# Flyback_Converter_SCHEMATIC.net
KiCad netlist of a schematic drawn in Altium Designer
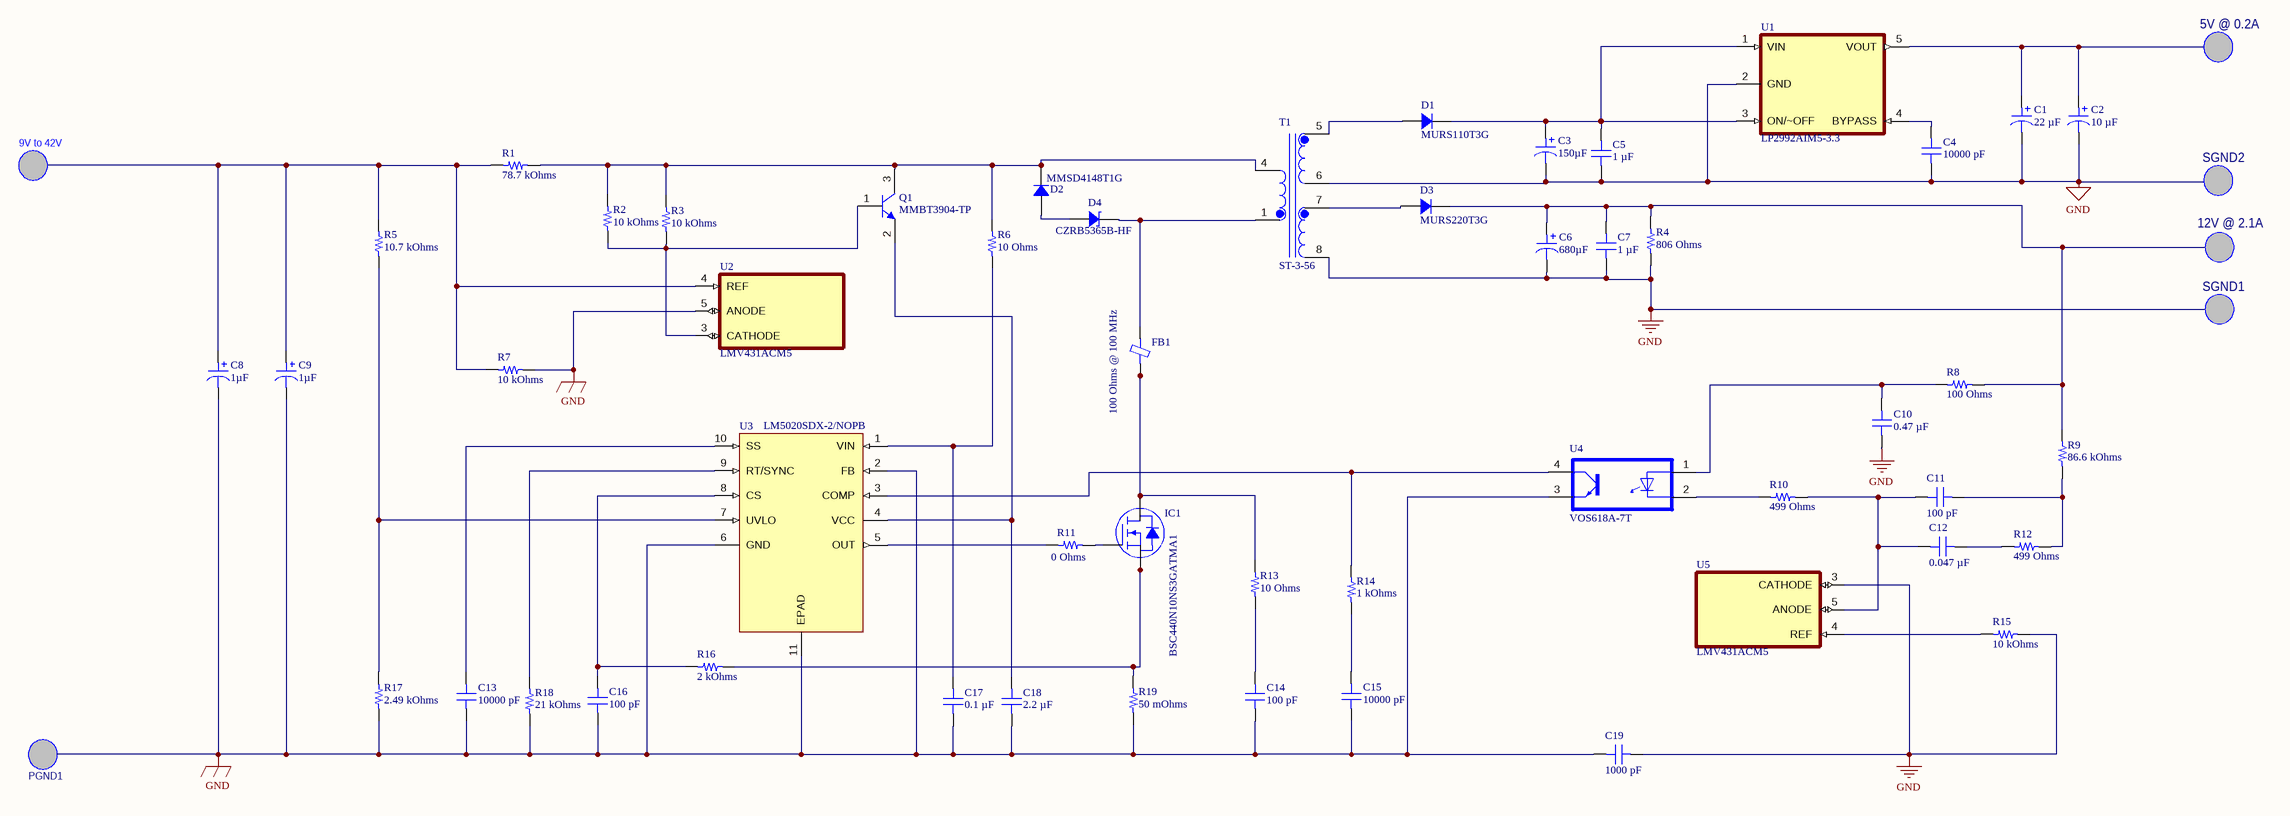
[diagram p0: Flyback Converter SCHEMATIC.SchDoc]

(export (version "E")
  (design (tool "Eeschema 10.0.6"))
  (components
    (comp (ref "C1")
      (value "22 µF")
      (footprint "CAP AL TH D8 L3.5 H12.5")
      (description "CAP ALUM 22UF 20% 100V RADIAL")
      (fields (field (name "PART NUMBER") "UPJ2A220MPD") (field (name "MANUFACTURER") "Nichicon"))
      (libsource (lib "Celestial Altium Library - altium_library") (part "Polarised Capacitor"))
    )
    (comp (ref "C2")
      (value "10 µF")
      (footprint "CAP AL TH D8 L3.5 H12.5")
      (description "CAP ALUM 10UF 20% 100V RADIAL")
      (fields (field (name "PART NUMBER") "UKL2A100MPD1TD") (field (name "MANUFACTURER") "Nichicon"))
      (libsource (lib "Celestial Altium Library - altium_library") (part "Polarised Capacitor"))
    )
    (comp (ref "C3")
      (value "150µF")
      (footprint "CAP TH ALUM ELEC D8.00mm S3.50mm H13.00mm")
      (description "CAP ALUM 150UF 20% 35V RADIAL")
      (fields
        (field (name "PART NUMBER") "EKZE350ELL151MHB5D")
        (field (name "MANUFACTURER") "United Chemi-Con")
      )
      (libsource (lib "Celestial Altium Library - altium_library") (part "Polarised Capacitor"))
    )
    (comp (ref "C4")
      (value "10000 pF")
      (footprint "CAP 1206_3216 - 0.8MM")
      (description "CAP CER 1206 10NF 200V X7R 10%")
      (fields (field (name "PART NUMBER") "C1206C103K2REC7800") (field (name "MANUFACTURER") "KEMET"))
      (libsource (lib "Celestial Altium Library - altium_library") (part "Capacitor"))
    )
    (comp (ref "C5")
      (value "1 µF")
      (footprint "CAP 1206_3216 - 0.8MM")
      (description "CAP CER 1UF 100V X7R 1206")
      (fields (field (name "PART NUMBER") "C1206C105K1RACAUTO") (field (name "MANUFACTURER") "KEMET"))
      (libsource (lib "Celestial Altium Library - altium_library") (part "Capacitor"))
    )
    (comp (ref "C6")
      (value "680µF")
      (footprint "CAP TH ALUM ELEC D10.00mm S5.00mm H14.00mm")
      (description "CAP ALUM 680UF 20% 25V RADIAL")
      (fields (field (name "PART NUMBER") "25PX680MEFC10X12.5") (field (name "MANUFACTURER") "Rubycon"))
      (libsource (lib "Celestial Altium Library - altium_library") (part "Polarised Capacitor"))
    )
    (comp (ref "C7")
      (value "1 µF")
      (footprint "CAP 1206_3216 - 0.8MM")
      (description "CAP CER 1UF 100V X7R 1206")
      (fields (field (name "PART NUMBER") "C1206C105K1RACAUTO") (field (name "MANUFACTURER") "KEMET"))
      (libsource (lib "Celestial Altium Library - altium_library") (part "Capacitor"))
    )
    (comp (ref "C8")
      (value "1µF")
      (footprint "CAP TH ALUM ELEC D5.00mm S2.00mm H12.50mm")
      (description "CAP ALUM 1UF 20% 100V RADIAL")
      (fields (field (name "PART NUMBER") "UVP2A010MDD") (field (name "MANUFACTURER") "Nichicon"))
      (libsource (lib "Celestial Altium Library - altium_library") (part "Polarised Capacitor"))
    )
    (comp (ref "C9")
      (value "1µF")
      (footprint "CAP TH ALUM ELEC D5.00mm S2.00mm H12.50mm")
      (description "CAP ALUM 1UF 20% 100V RADIAL")
      (fields (field (name "PART NUMBER") "UVP2A010MDD") (field (name "MANUFACTURER") "Nichicon"))
      (libsource (lib "Celestial Altium Library - altium_library") (part "Polarised Capacitor"))
    )
    (comp (ref "C10")
      (value "0.47 µF")
      (footprint "CAP 1206_3216 - 0.8MM")
      (description "CAP CER 0.47UF 100V X7R 1206")
      (fields
        (field (name "PART NUMBER") "CGA5L2X7R2A474M160AE")
        (field (name "MANUFACTURER") "TDK Corporation")
      )
      (libsource (lib "Celestial Altium Library - altium_library") (part "Capacitor"))
    )
    (comp (ref "C11")
      (value "100 pF")
      (footprint "CAP 1206_3216 - 0.8MM")
      (description "CAP CER 100PF 100V X8R 1206")
      (fields (field (name "PART NUMBER") "C1206C101F1HAC7800") (field (name "MANUFACTURER") "KEMET"))
      (libsource (lib "Celestial Altium Library - altium_library") (part "Capacitor"))
    )
    (comp (ref "C12")
      (value "0.047 µF")
      (footprint "CAP 1206_3216 - 0.8MM")
      (description "CAP CER 1206 47NF 250V X7R 10%")
      (fields (field (name "PART NUMBER") "C1206C473KAREC7800") (field (name "MANUFACTURER") "KEMET"))
      (libsource (lib "Celestial Altium Library - altium_library") (part "Capacitor"))
    )
    (comp (ref "C13")
      (value "10000 pF")
      (footprint "CAP 1206_3216 - 0.8MM")
      (description "CAP CER 1206 10NF 200V X7R 10%")
      (fields (field (name "PART NUMBER") "C1206C103K2REC7800") (field (name "MANUFACTURER") "KEMET"))
      (libsource (lib "Celestial Altium Library - altium_library") (part "Capacitor"))
    )
    (comp (ref "C14")
      (value "100 pF")
      (footprint "CAP 1206_3216 - 0.8MM")
      (description "CAP CER 100PF 100V C0G/NP0 1206")
      (fields (field (name "PART NUMBER") "C1206C101K1GAC7800") (field (name "MANUFACTURER") "KEMET"))
      (libsource (lib "Celestial Altium Library - altium_library") (part "Capacitor"))
    )
    (comp (ref "C15")
      (value "10000 pF")
      (footprint "CAP 1206_3216 - 0.8MM")
      (description "CAP CER 1206 10NF 200V X7R 10%")
      (fields (field (name "PART NUMBER") "C1206C103K2REC7800") (field (name "MANUFACTURER") "KEMET"))
      (libsource (lib "Celestial Altium Library - altium_library") (part "Capacitor"))
    )
    (comp (ref "C16")
      (value "100 pF")
      (footprint "CAP 1206_3216 - 0.8MM")
      (description "CAP CER 100PF 100V C0G/NP0 1206")
      (fields (field (name "PART NUMBER") "C1206C101K1GAC7800") (field (name "MANUFACTURER") "KEMET"))
      (libsource (lib "Celestial Altium Library - altium_library") (part "Capacitor"))
    )
    (comp (ref "C17")
      (value "0.1 µF")
      (footprint "CAP 1206_3216 - 0.8MM")
      (description "SMD AUTO X7R FE, CERAMIC, 0.1 UF")
      (fields (field (name "PART NUMBER") "C1206S104K5RACAUTO") (field (name "MANUFACTURER") "KEMET"))
      (libsource (lib "Celestial Altium Library - altium_library") (part "Capacitor"))
    )
    (comp (ref "C18")
      (value "2.2 µF")
      (footprint "CAP 1206_3216 - 0.8MM")
      (description "SMD AUTO X7R FO, CERAMIC, 2.2 UF")
      (fields (field (name "PART NUMBER") "C1206J225J4RACAUTO") (field (name "MANUFACTURER") "KEMET"))
      (libsource (lib "Celestial Altium Library - altium_library") (part "Capacitor"))
    )
    (comp (ref "C19")
      (value "1000 pF")
      (footprint "CAP 1206_3216 - 0.8MM")
      (description "CAP CER 1206 1NF 200V C0G 2%")
      (fields (field (name "PART NUMBER") "C1206C102G2GECAUTO") (field (name "MANUFACTURER") "KEMET"))
      (libsource (lib "Celestial Altium Library - altium_library") (part "Capacitor"))
    )
    (comp (ref "D1")
      (value "MURS110T3G")
      (footprint "DO214AA SMB")
      (description "DIODE GEN PURP 100V 2A SMB")
      (fields (field (name "MANUFACTURER") "ON Semiconductor"))
      (libsource (lib "Celestial Altium Library - altium_library") (part "Diode"))
    )
    (comp (ref "D2")
      (value "MMSD4148T1G")
      (footprint "SOD-123")
      (description "DIODE GEN PURP 100V 200MA SOD123")
      (fields (field (name "MANUFACTURER") "ON Semiconductor"))
      (libsource (lib "Celestial Altium Library - altium_library") (part "Diode"))
    )
    (comp (ref "D3")
      (value "MURS220T3G")
      (footprint "DO214AA SMB")
      (description "DIODE GEN PURP 200V 2A SMB")
      (fields (field (name "MANUFACTURER") "ON Semiconductor"))
      (libsource (lib "Celestial Altium Library - altium_library") (part "Diode"))
    )
    (comp (ref "D4")
      (value "CZRB5365B-HF")
      (footprint "DO214AA SMB")
      (description "DIODE ZENER 36V 5W DO214AA")
      (fields (field (name "MANUFACTURER") "Comchip Technology") (field (name "TOLERANCE") "±5%"))
      (libsource (lib "Celestial Altium Library - altium_library") (part "Diode Zener"))
    )
    (comp (ref "FB1")
      (value "100 Ohms @ 100 MHz")
      (footprint "FER 1206_3216")
      (description "FIXED IND 100 3000MA 1206")
      (fields
        (field (name "PART NUMBER") "MFBW1V3216-101-R")
        (field (name "MANUFACTURER") "Eaton - Electronics Division")
      )
      (libsource (lib "Celestial Altium Library - altium_library") (part "Ferrite Chip"))
    )
    (comp (ref "IC1")
      (value "BSC440N10NS3GATMA1")
      (footprint "INFINEON PG-TDSON-8 6.15X5.32MM")
      (description "MOSFET N-CH 100V 5.3A/18A TDSON")
      (fields (field (name "MANUFACTURER") "Infineon Technologies"))
      (libsource (lib "Celestial Altium Library - altium_library") (part "INFINEON BSC MOSFET N-CH"))
    )
    (comp (ref "Q1")
      (value "MMBT3904-TP")
      (footprint "MCCSEMI SOT-23-3")
      (description "TRANS NPN 40V 0.2A SOT23")
      (fields (field (name "MANUFACTURER") "Micro Commercial Co"))
      (libsource (lib "Celestial Altium Library - altium_library") (part "MCCSEMI NPN SOT-23-3"))
    )
    (comp (ref "R1")
      (value "78.7 kOhms")
      (footprint "RES 1206_3216")
      (description "RES SMD 78.7K OHM 1% 1/4W 1206")
      (fields (field (name "PART NUMBER") "CRCW120678K7FKEA") (field (name "MANUFACTURER") "Vishay Dale"))
      (libsource (lib "Celestial Altium Library - altium_library") (part "Resistor"))
    )
    (comp (ref "R2")
      (value "10 kOhms")
      (footprint "RES 1206_3216")
      (description "RES SMD 10K OHM 1% 1/4W 1206")
      (fields
        (field (name "PART NUMBER") "CRG1206F10K")
        (field (name "MANUFACTURER") "TE Connectivity Passive Product")
      )
      (libsource (lib "Celestial Altium Library - altium_library") (part "Resistor"))
    )
    (comp (ref "R3")
      (value "10 kOhms")
      (footprint "RES 1206_3216")
      (description "RES SMD 10K OHM 1% 1/4W 1206")
      (fields
        (field (name "PART NUMBER") "CRG1206F10K")
        (field (name "MANUFACTURER") "TE Connectivity Passive Product")
      )
      (libsource (lib "Celestial Altium Library - altium_library") (part "Resistor"))
    )
    (comp (ref "R4")
      (value "806 Ohms")
      (footprint "RES 1206_3216")
      (description "RES SMD 806 OHM 1% 1/4W 1206")
      (fields (field (name "PART NUMBER") "CRCW1206806RFKEA") (field (name "MANUFACTURER") "Vishay Dale"))
      (libsource (lib "Celestial Altium Library - altium_library") (part "Resistor"))
    )
    (comp (ref "R5")
      (value "10.7 kOhms")
      (footprint "RES 1206_3216")
      (description "RES 10.7K OHM 1% 1/4W 1206")
      (fields (field (name "PART NUMBER") "RC1206FR-0710K7L") (field (name "MANUFACTURER") "Yageo"))
      (libsource (lib "Celestial Altium Library - altium_library") (part "Resistor"))
    )
    (comp (ref "R6")
      (value "10 Ohms")
      (footprint "RES 1206_3216")
      (description "RES SMD 10 OHM 1% 1/4W 1206")
      (fields (field (name "PART NUMBER") "CRCW120610R0FKEB") (field (name "MANUFACTURER") "Vishay Dale"))
      (libsource (lib "Celestial Altium Library - altium_library") (part "Resistor"))
    )
    (comp (ref "R7")
      (value "10 kOhms")
      (footprint "RES 1206_3216")
      (description "RES SMD 10K OHM 1% 1/4W 1206")
      (fields
        (field (name "PART NUMBER") "CRG1206F10K")
        (field (name "MANUFACTURER") "TE Connectivity Passive Product")
      )
      (libsource (lib "Celestial Altium Library - altium_library") (part "Resistor"))
    )
    (comp (ref "R8")
      (value "100 Ohms")
      (footprint "RES 1206_3216")
      (description "RES SMD 100 OHM 1% 1/4W 1206")
      (fields (field (name "PART NUMBER") "CRCW1206100RFKEB") (field (name "MANUFACTURER") "Vishay Dale"))
      (libsource (lib "Celestial Altium Library - altium_library") (part "Resistor"))
    )
    (comp (ref "R9")
      (value "86.6 kOhms")
      (footprint "RES 1206_3216")
      (description "RES SMD 86.6K OHM 1% 1/4W 1206")
      (fields (field (name "PART NUMBER") "CRCW120686K6FKEA") (field (name "MANUFACTURER") "Vishay Dale"))
      (libsource (lib "Celestial Altium Library - altium_library") (part "Resistor"))
    )
    (comp (ref "R10")
      (value "499 Ohms")
      (footprint "RES 1206_3216")
      (description "RES SMD 499 OHM 1% 1/4W 1206")
      (fields (field (name "PART NUMBER") "CR1206-FX-4990ELF") (field (name "MANUFACTURER") "Bourns Inc."))
      (libsource (lib "Celestial Altium Library - altium_library") (part "Resistor"))
    )
    (comp (ref "R11")
      (value "0 Ohms")
      (footprint "RES 1206_3216")
      (description "RES SMD 0 OHM JUMPER 1/4W 1206")
      (fields (field (name "PART NUMBER") "CRCW12060000ZSTA") (field (name "MANUFACTURER") "Vishay Dale"))
      (libsource (lib "Celestial Altium Library - altium_library") (part "Resistor"))
    )
    (comp (ref "R12")
      (value "499 Ohms")
      (footprint "RES 1206_3216")
      (description "RES SMD 499 OHM 1% 1/4W 1206")
      (fields (field (name "PART NUMBER") "CR1206-FX-4990ELF") (field (name "MANUFACTURER") "Bourns Inc."))
      (libsource (lib "Celestial Altium Library - altium_library") (part "Resistor"))
    )
    (comp (ref "R13")
      (value "10 Ohms")
      (footprint "RES 1206_3216")
      (description "RES SMD 10 OHM 1% 1/4W 1206")
      (fields (field (name "PART NUMBER") "CRCW120610R0FKEB") (field (name "MANUFACTURER") "Vishay Dale"))
      (libsource (lib "Celestial Altium Library - altium_library") (part "Resistor"))
    )
    (comp (ref "R14")
      (value "1 kOhms")
      (footprint "RES 1206_3216")
      (description "RES 1K OHM 1% 1/4W 1206")
      (fields (field (name "PART NUMBER") "CRCW12061K00FKEBC") (field (name "MANUFACTURER") "Vishay Dale"))
      (libsource (lib "Celestial Altium Library - altium_library") (part "Resistor"))
    )
    (comp (ref "R15")
      (value "10 kOhms")
      (footprint "RES 1206_3216")
      (description "RES SMD 10K OHM 1% 1/4W 1206")
      (fields
        (field (name "PART NUMBER") "CRG1206F10K")
        (field (name "MANUFACTURER") "TE Connectivity Passive Product")
      )
      (libsource (lib "Celestial Altium Library - altium_library") (part "Resistor"))
    )
    (comp (ref "R16")
      (value "2 kOhms")
      (footprint "RES 1206_3216")
      (description "RES SMD 2K OHM 1% 1/4W 1206")
      (fields (field (name "PART NUMBER") "CRCW12062K00FKEA") (field (name "MANUFACTURER") "Vishay Dale"))
      (libsource (lib "Celestial Altium Library - altium_library") (part "Resistor"))
    )
    (comp (ref "R17")
      (value "2.49 kOhms")
      (footprint "RES 1206_3216")
      (description "RES SMD 2.49K OHM 1% 1/4W 1206")
      (fields (field (name "PART NUMBER") "CRCW12062K49FKEA") (field (name "MANUFACTURER") "Vishay Dale"))
      (libsource (lib "Celestial Altium Library - altium_library") (part "Resistor"))
    )
    (comp (ref "R18")
      (value "21 kOhms")
      (footprint "RES 1206_3216")
      (description "RES SMD 21K OHM 1% 1/4W 1206")
      (fields (field (name "PART NUMBER") "CRCW120621K0FKEA") (field (name "MANUFACTURER") "Vishay Dale"))
      (libsource (lib "Celestial Altium Library - altium_library") (part "Resistor"))
    )
    (comp (ref "R19")
      (value "50 mOhms")
      (footprint "RES 1206_3216")
      (description "RES 0.05 OHM 1% 1/4W 1206")
      (fields (field (name "PART NUMBER") "RL1206FR-070R05L") (field (name "MANUFACTURER") "Yageo"))
      (libsource (lib "Celestial Altium Library - altium_library") (part "Resistor"))
    )
    (comp (ref "T1")
      (value "ST-3-56")
      (footprint "Flyback Transformer:flyback tranformer")
      (description "Split Bobbin Low Power Transformer ¦ 2.4VA Power ¦ 115V Input ¦ 10VCT Output Series")
      (libsource (lib "ST-3-56") (part "ST-3-56"))
    )
    (comp (ref "U1")
      (value "LP2992AIM5-3.3")
      (footprint "SOT95P280X145-5N:SOT95P280X145-5N")
      (libsource (lib "LP2992AIM5-3.3") (part "LP2992AIM5-3.3"))
    )
    (comp (ref "U2")
      (value "LMV431ACM5")
      (footprint "SOT95P280X145-5N-1:SOT95P280X145-5N")
      (description "1%, low-voltage (1.24-V) adjustable precision shunt regulator 5-SOT-23 0 to 70")
      (fields (field (name "MF") "Texas Instruments"))
      (libsource (lib "") (part "LMV431ACM5_1"))
    )
    (comp (ref "U3")
      (value "LM5020SDX-2/NOPB")
      (footprint "DFN400X400X80-11N:DFN400X400X80-11N")
      (description "13-100V Wide Vin, Current Mode PWM Boost, Flyback, Sepic Controller")
      (fields (field (name "MF") "Texas Instruments"))
      (libsource (lib "LM5020SDX-2_NOPB") (part "LM5020SDX-2/NOPB"))
    )
    (comp (ref "U4")
      (value "VOS618A-7T")
      (footprint "SOIC127P700X210-4N:SOIC127P700X210-4N")
      (description "Optoisolator Transistor Output 3750Vrms 1 Channel 4-SSOP")
      (fields (field (name "MF") "Vishay"))
      (libsource (lib "VOS618A-7T") (part "VOS618A-7T"))
    )
    (comp (ref "U5")
      (value "LMV431ACM5")
      (footprint "SOT95P280X145-5N-1:SOT95P280X145-5N")
      (description "1%, low-voltage (1.24-V) adjustable precision shunt regulator 5-SOT-23 0 to 70")
      (fields (field (name "MF") "Texas Instruments"))
      (libsource (lib "LMV431ACM5") (part "LMV431ACM5"))
    )
  )
  (nets
    (net (code "1") (name "GND") (class "Default")
      (node (ref "C1") (pin "2") (pinfunction "2_2") (pintype "passive"))
      (node (ref "C10") (pin "1") (pinfunction "1_1") (pintype "passive"))
      (node (ref "C13") (pin "1") (pinfunction "1_1") (pintype "passive"))
      (node (ref "C14") (pin "1") (pinfunction "1_1") (pintype "passive"))
      (node (ref "C15") (pin "1") (pinfunction "1_1") (pintype "passive"))
      (node (ref "C16") (pin "1") (pinfunction "1_1") (pintype "passive"))
      (node (ref "C17") (pin "1") (pinfunction "1_1") (pintype "passive"))
      (node (ref "C18") (pin "1") (pinfunction "1_1") (pintype "passive"))
      (node (ref "C19") (pin "1") (pinfunction "1_1") (pintype "passive"))
      (node (ref "C19") (pin "2") (pinfunction "2_2") (pintype "passive"))
      (node (ref "C2") (pin "2") (pinfunction "2_2") (pintype "passive"))
      (node (ref "C3") (pin "2") (pinfunction "2_2") (pintype "passive"))
      (node (ref "C4") (pin "1") (pinfunction "1_1") (pintype "passive"))
      (node (ref "C5") (pin "1") (pinfunction "1_1") (pintype "passive"))
      (node (ref "C6") (pin "2") (pinfunction "2_2") (pintype "passive"))
      (node (ref "C7") (pin "1") (pinfunction "1_1") (pintype "passive"))
      (node (ref "C8") (pin "2") (pinfunction "2_2") (pintype "passive"))
      (node (ref "C9") (pin "2") (pinfunction "2_2") (pintype "passive"))
      (node (ref "R15") (pin "1") (pinfunction "1_1") (pintype "passive"))
      (node (ref "R17") (pin "1") (pinfunction "1_1") (pintype "passive"))
      (node (ref "R18") (pin "1") (pinfunction "1_1") (pintype "passive"))
      (node (ref "R19") (pin "1") (pinfunction "1_1") (pintype "passive"))
      (node (ref "R4") (pin "1") (pinfunction "1_1") (pintype "passive"))
      (node (ref "R7") (pin "2") (pinfunction "2_2") (pintype "passive"))
      (node (ref "T1") (pin "6") (pinfunction "6_6") (pintype "passive"))
      (node (ref "T1") (pin "8") (pinfunction "8_8") (pintype "passive"))
      (node (ref "U1") (pin "2") (pinfunction "GND_2") (pintype "power_in"))
      (node (ref "U2") (pin "5") (pinfunction "ANODE_5") (pintype "bidirectional"))
      (node (ref "U3") (pin "11") (pinfunction "EPAD_11") (pintype "passive"))
      (node (ref "U3") (pin "2") (pinfunction "FB_2") (pintype "input"))
      (node (ref "U3") (pin "6") (pinfunction "GND_6") (pintype "passive"))
      (node (ref "U4") (pin "3") (pinfunction "E_3") (pintype "passive"))
      (node (ref "U5") (pin "3") (pinfunction "CATHODE_3") (pintype "bidirectional"))
    )
    (net (code "2") (name "Net-(C6-Pad1)") (class "Default")
      (node (ref "C6") (pin "1") (pinfunction "1_1") (pintype "passive"))
      (node (ref "C7") (pin "2") (pinfunction "2_2") (pintype "passive"))
      (node (ref "D3") (pin "2") (pinfunction "2_2") (pintype "passive"))
      (node (ref "R4") (pin "2") (pinfunction "2_2") (pintype "passive"))
      (node (ref "R8") (pin "1") (pinfunction "1_1") (pintype "passive"))
      (node (ref "R9") (pin "2") (pinfunction "2_2") (pintype "passive"))
    )
    (net (code "3") (name "Net-(C11-Pad2)") (class "Default")
      (node (ref "C11") (pin "2") (pinfunction "2_2") (pintype "passive"))
      (node (ref "R12") (pin "2") (pinfunction "2_2") (pintype "passive"))
      (node (ref "R9") (pin "1") (pinfunction "1_1") (pintype "passive"))
    )
    (net (code "4") (name "Net-(C12-Pad2)") (class "Default")
      (node (ref "C12") (pin "2") (pinfunction "2_2") (pintype "passive"))
      (node (ref "R12") (pin "1") (pinfunction "1_1") (pintype "passive"))
    )
    (net (code "5") (name "Net-(C14-Pad2)") (class "Default")
      (node (ref "C14") (pin "2") (pinfunction "2_2") (pintype "passive"))
      (node (ref "R13") (pin "1") (pinfunction "1_1") (pintype "passive"))
    )
    (net (code "6") (name "Net-(C15-Pad2)") (class "Default")
      (node (ref "C15") (pin "2") (pinfunction "2_2") (pintype "passive"))
      (node (ref "R14") (pin "1") (pinfunction "1_1") (pintype "passive"))
    )
    (net (code "7") (name "Net-(D1-Pad1)") (class "Default")
      (node (ref "D1") (pin "1") (pinfunction "1_1") (pintype "passive"))
      (node (ref "T1") (pin "5") (pinfunction "5_5") (pintype "passive"))
    )
    (net (code "8") (name "Net-(D2-Pad1)") (class "Default")
      (node (ref "D2") (pin "1") (pinfunction "1_1") (pintype "passive"))
      (node (ref "D4") (pin "1") (pinfunction "1_1") (pintype "passive"))
    )
    (net (code "9") (name "Net-(D3-Pad1)") (class "Default")
      (node (ref "D3") (pin "1") (pinfunction "1_1") (pintype "passive"))
      (node (ref "T1") (pin "7") (pinfunction "7_7") (pintype "passive"))
    )
    (net (code "10") (name "Net-(D4-Pad2)") (class "Default")
      (node (ref "D4") (pin "2") (pinfunction "2_2") (pintype "passive"))
      (node (ref "FB1") (pin "2") (pinfunction "2_2") (pintype "passive"))
      (node (ref "T1") (pin "1") (pinfunction "1_1") (pintype "passive"))
    )
    (net (code "11") (name "Net-(FB1-Pad1)") (class "Default")
      (node (ref "FB1") (pin "1") (pinfunction "1_1") (pintype "passive"))
      (node (ref "IC1") (pin "5") (pinfunction "D_5") (pintype "passive"))
      (node (ref "IC1") (pin "6") (pinfunction "D_6") (pintype "passive"))
      (node (ref "IC1") (pin "7") (pinfunction "D_7") (pintype "passive"))
      (node (ref "IC1") (pin "8") (pinfunction "D_8") (pintype "passive"))
      (node (ref "R13") (pin "2") (pinfunction "2_2") (pintype "passive"))
    )
    (net (code "12") (name "Net-(IC1-G)") (class "Default")
      (node (ref "IC1") (pin "4") (pinfunction "G_4") (pintype "passive"))
      (node (ref "R11") (pin "2") (pinfunction "2_2") (pintype "passive"))
    )
    (net (code "13") (name "Net-(IC1-S-Pad1)") (class "Default")
      (node (ref "IC1") (pin "1") (pinfunction "S_1") (pintype "passive"))
      (node (ref "IC1") (pin "2") (pinfunction "S_2") (pintype "passive"))
      (node (ref "IC1") (pin "3") (pinfunction "S_3") (pintype "passive"))
      (node (ref "R16") (pin "2") (pinfunction "2_2") (pintype "passive"))
      (node (ref "R19") (pin "2") (pinfunction "2_2") (pintype "passive"))
    )
    (net (code "14") (name "Net-(Q1-B)") (class "Default")
      (node (ref "Q1") (pin "1") (pinfunction "B_1") (pintype "passive"))
      (node (ref "R2") (pin "1") (pinfunction "1_1") (pintype "passive"))
      (node (ref "R3") (pin "1") (pinfunction "1_1") (pintype "passive"))
      (node (ref "U2") (pin "3") (pinfunction "CATHODE_3") (pintype "bidirectional"))
    )
    (net (code "15") (name "Net-(Q1-C)") (class "Default")
      (node (ref "D2") (pin "2") (pinfunction "2_2") (pintype "passive"))
      (node (ref "Q1") (pin "3") (pinfunction "C_3") (pintype "passive"))
      (node (ref "R1") (pin "2") (pinfunction "2_2") (pintype "passive"))
      (node (ref "R2") (pin "2") (pinfunction "2_2") (pintype "passive"))
      (node (ref "R3") (pin "2") (pinfunction "2_2") (pintype "passive"))
      (node (ref "R6") (pin "2") (pinfunction "2_2") (pintype "passive"))
      (node (ref "T1") (pin "4") (pinfunction "4_4") (pintype "passive"))
    )
    (net (code "16") (name "Net-(Q1-E)") (class "Default")
      (node (ref "C18") (pin "2") (pinfunction "2_2") (pintype "passive"))
      (node (ref "Q1") (pin "2") (pinfunction "E_2") (pintype "passive"))
      (node (ref "U3") (pin "4") (pinfunction "VCC_4") (pintype "power_in"))
    )
    (net (code "17") (name "Net-(U1-BYPASS)") (class "Default")
      (node (ref "C4") (pin "2") (pinfunction "2_2") (pintype "passive"))
      (node (ref "U1") (pin "4") (pinfunction "BYPASS_4") (pintype "input"))
    )
    (net (code "18") (name "Net-(U1-ON{slash}~OFF)") (class "Default")
      (node (ref "C3") (pin "1") (pinfunction "1_1") (pintype "passive"))
      (node (ref "C5") (pin "2") (pinfunction "2_2") (pintype "passive"))
      (node (ref "D1") (pin "2") (pinfunction "2_2") (pintype "passive"))
      (node (ref "U1") (pin "1") (pinfunction "VIN_1") (pintype "input"))
      (node (ref "U1") (pin "3") (pinfunction "ON/~OFF_3") (pintype "input"))
    )
    (net (code "19") (name "Net-(U1-VOUT)") (class "Default")
      (node (ref "C1") (pin "1") (pinfunction "1_1") (pintype "passive"))
      (node (ref "C2") (pin "1") (pinfunction "1_1") (pintype "passive"))
      (node (ref "U1") (pin "5") (pinfunction "VOUT_5") (pintype "output"))
    )
    (net (code "20") (name "Net-(U2-REF)") (class "Default")
      (node (ref "C8") (pin "1") (pinfunction "1_1") (pintype "passive"))
      (node (ref "C9") (pin "1") (pinfunction "1_1") (pintype "passive"))
      (node (ref "R1") (pin "1") (pinfunction "1_1") (pintype "passive"))
      (node (ref "R5") (pin "2") (pinfunction "2_2") (pintype "passive"))
      (node (ref "R7") (pin "1") (pinfunction "1_1") (pintype "passive"))
      (node (ref "U2") (pin "4") (pinfunction "REF_4") (pintype "input"))
    )
    (net (code "21") (name "Net-(U3-COMP)") (class "Default")
      (node (ref "R14") (pin "2") (pinfunction "2_2") (pintype "passive"))
      (node (ref "U3") (pin "3") (pinfunction "COMP_3") (pintype "input"))
      (node (ref "U4") (pin "4") (pinfunction "CO_4") (pintype "passive"))
    )
    (net (code "22") (name "Net-(U3-CS)") (class "Default")
      (node (ref "C16") (pin "2") (pinfunction "2_2") (pintype "passive"))
      (node (ref "R16") (pin "1") (pinfunction "1_1") (pintype "passive"))
      (node (ref "U3") (pin "8") (pinfunction "CS_8") (pintype "input"))
    )
    (net (code "23") (name "Net-(U3-OUT)") (class "Default")
      (node (ref "R11") (pin "1") (pinfunction "1_1") (pintype "passive"))
      (node (ref "U3") (pin "5") (pinfunction "OUT_5") (pintype "output"))
    )
    (net (code "24") (name "Net-(U3-RT{slash}SYNC)") (class "Default")
      (node (ref "R18") (pin "2") (pinfunction "2_2") (pintype "passive"))
      (node (ref "U3") (pin "9") (pinfunction "RT/SYNC_9") (pintype "input"))
    )
    (net (code "25") (name "Net-(U3-SS)") (class "Default")
      (node (ref "C13") (pin "2") (pinfunction "2_2") (pintype "passive"))
      (node (ref "U3") (pin "10") (pinfunction "SS_10") (pintype "input"))
    )
    (net (code "26") (name "Net-(U3-UVLO)") (class "Default")
      (node (ref "R17") (pin "2") (pinfunction "2_2") (pintype "passive"))
      (node (ref "R5") (pin "1") (pinfunction "1_1") (pintype "passive"))
      (node (ref "U3") (pin "7") (pinfunction "UVLO_7") (pintype "input"))
    )
    (net (code "27") (name "Net-(U3-VIN)") (class "Default")
      (node (ref "C17") (pin "2") (pinfunction "2_2") (pintype "passive"))
      (node (ref "R6") (pin "1") (pinfunction "1_1") (pintype "passive"))
      (node (ref "U3") (pin "1") (pinfunction "VIN_1") (pintype "input"))
    )
    (net (code "28") (name "Net-(U4-A)") (class "Default")
      (node (ref "C10") (pin "2") (pinfunction "2_2") (pintype "passive"))
      (node (ref "R8") (pin "2") (pinfunction "2_2") (pintype "passive"))
      (node (ref "U4") (pin "1") (pinfunction "A_1") (pintype "passive"))
    )
    (net (code "29") (name "Net-(U4-C)") (class "Default")
      (node (ref "R10") (pin "1") (pinfunction "1_1") (pintype "passive"))
      (node (ref "U4") (pin "2") (pinfunction "C_2") (pintype "passive"))
    )
    (net (code "30") (name "Net-(U5-ANODE)") (class "Default")
      (node (ref "C11") (pin "1") (pinfunction "1_1") (pintype "passive"))
      (node (ref "C12") (pin "1") (pinfunction "1_1") (pintype "passive"))
      (node (ref "R10") (pin "2") (pinfunction "2_2") (pintype "passive"))
      (node (ref "U5") (pin "5") (pinfunction "ANODE_5") (pintype "bidirectional"))
    )
    (net (code "31") (name "Net-(U5-REF)") (class "Default")
      (node (ref "R15") (pin "2") (pinfunction "2_2") (pintype "passive"))
      (node (ref "U5") (pin "4") (pinfunction "REF_4") (pintype "input"))
    )
  )
)
